# nav10_mxp_3_3_final_expio.net
KiCad netlist of a schematic drawn in EAGLE
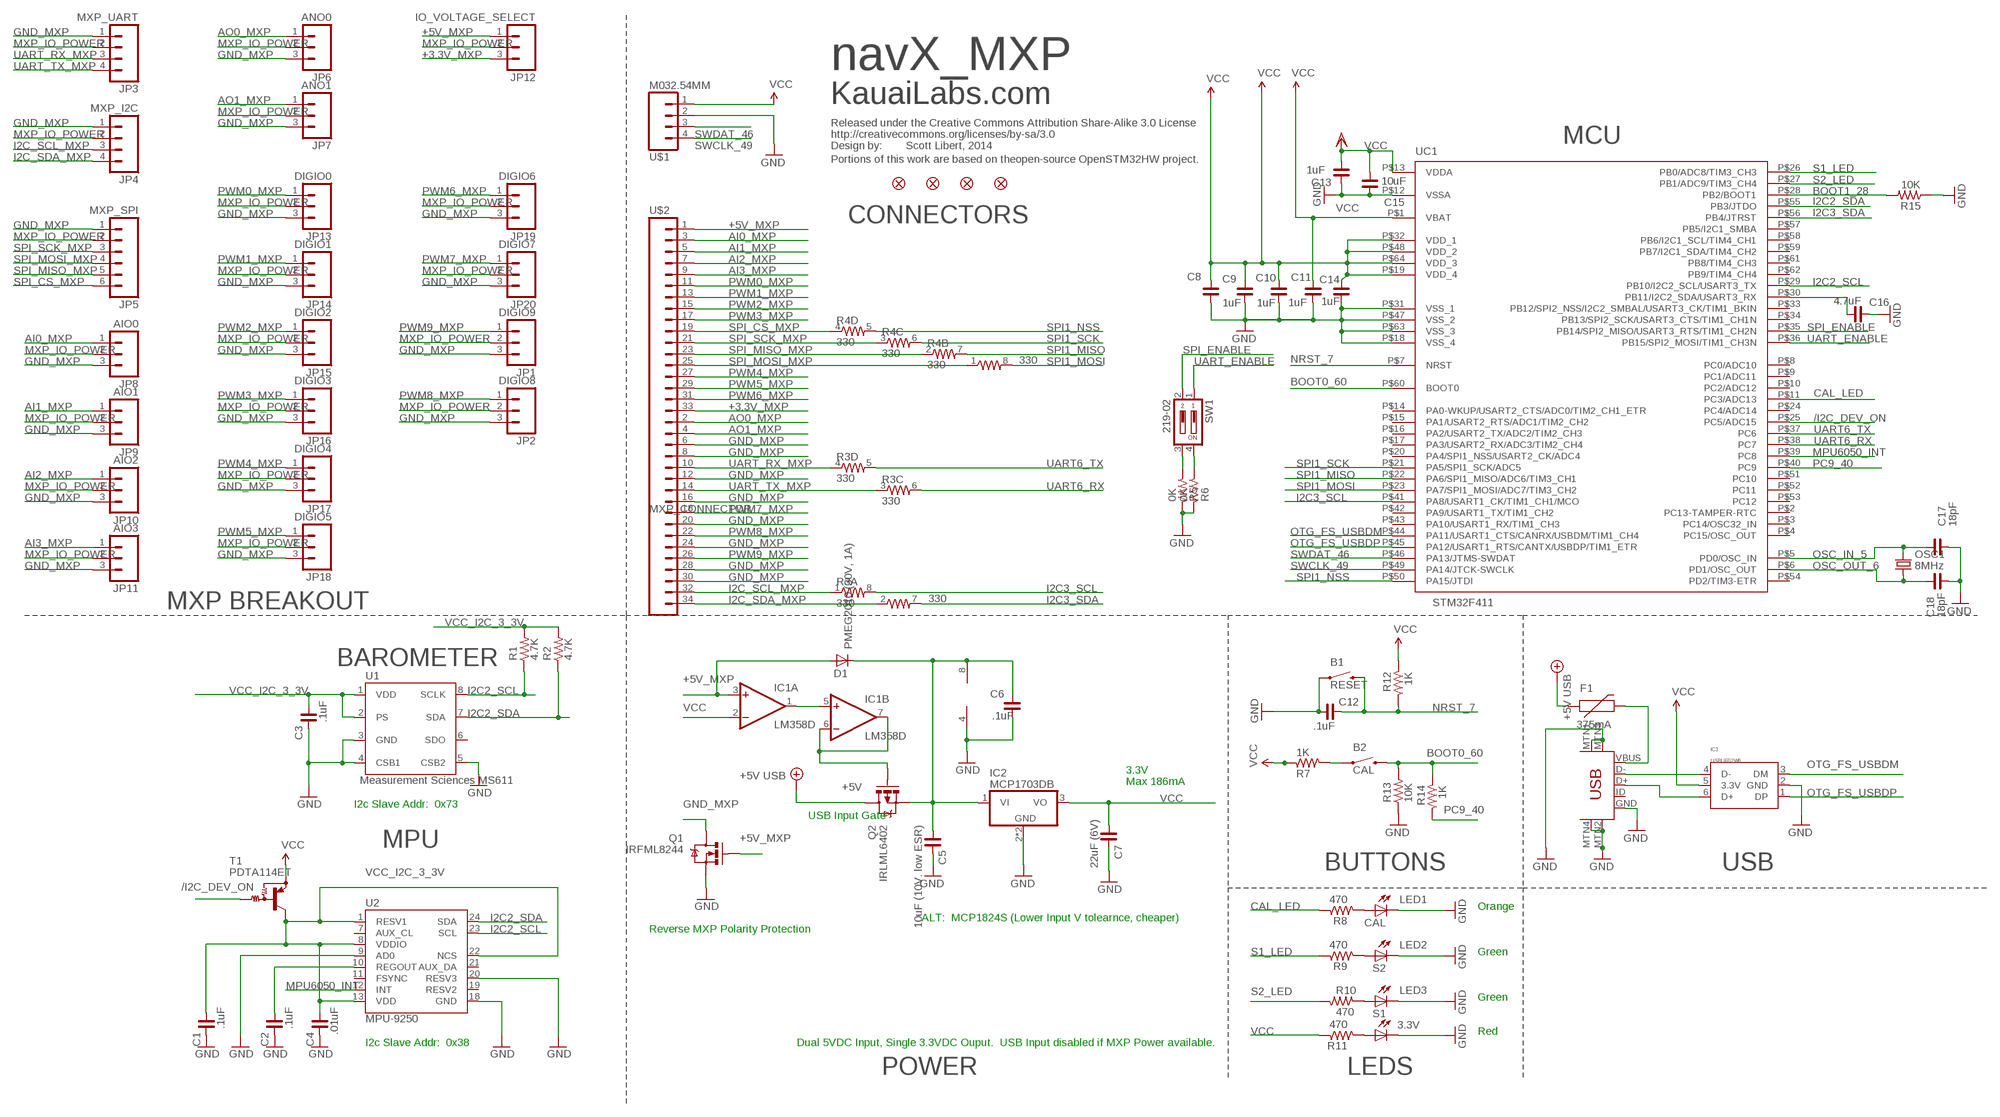
[diagram p0: schematic, sheet 1]

(export (version "E")
  (design (tool "Eeschema 10.0.6"))
  (components
    (comp (ref "B1")
      (value "RESET")
      (footprint "eagle-import:TACTILE-SWITCH-1101NE")
      (libsource (lib "eagle-import") (part "SWITCH-MOMENTARY-2-SMD-1101NE"))
    )
    (comp (ref "B2")
      (value "CAL")
      (footprint "eagle-import:TACTILE-SWITCH-1101NE")
      (libsource (lib "eagle-import") (part "SWITCH-MOMENTARY-2-SMD-1101NE"))
    )
    (comp (ref "C1")
      (value ".1uF")
      (footprint "eagle-import:C0603")
      (libsource (lib "eagle-import") (part "C_0603"))
    )
    (comp (ref "C2")
      (value ".1uF")
      (footprint "eagle-import:C0603")
      (libsource (lib "eagle-import") (part "C_0603"))
    )
    (comp (ref "C3")
      (value ".1uF")
      (footprint "eagle-import:C0603")
      (fields (field (name "DIGIKEY_PART_NUMBER") "399-1096-1-ND"))
      (libsource (lib "eagle-import") (part "C_0603"))
    )
    (comp (ref "C4")
      (value ".01uF")
      (footprint "eagle-import:C0603")
      (libsource (lib "eagle-import") (part "C_0603"))
    )
    (comp (ref "C5")
      (value "10uF (10V. low ESR)")
      (footprint "eagle-import:C0805")
      (fields (field (name "DIGIKEY_PART_NUMBER") "399-1158-1-ND"))
      (libsource (lib "eagle-import") (part "C_0805"))
    )
    (comp (ref "C6")
      (value ".1uF")
      (footprint "eagle-import:C0603")
      (libsource (lib "eagle-import") (part "C_0603"))
    )
    (comp (ref "C7")
      (value "22uF (6V)")
      (footprint "eagle-import:C0805")
      (fields (field (name "DIGIKEY_PART_NUMBER") "399-1158-1-ND"))
      (libsource (lib "eagle-import") (part "C_0805"))
    )
    (comp (ref "C8")
      (value "1uF")
      (footprint "eagle-import:C0603")
      (fields (field (name "DIGIKEY_PART_NUMBER") "399-3118-1-ND"))
      (libsource (lib "eagle-import") (part "C_0603"))
    )
    (comp (ref "C9")
      (value "1uF")
      (footprint "eagle-import:C0603")
      (libsource (lib "eagle-import") (part "C_0603"))
    )
    (comp (ref "C10")
      (value "1uF")
      (footprint "eagle-import:C0603")
      (libsource (lib "eagle-import") (part "C_0603"))
    )
    (comp (ref "C11")
      (value "1uF")
      (footprint "eagle-import:C0603")
      (libsource (lib "eagle-import") (part "C_0603"))
    )
    (comp (ref "C12")
      (value ".1uF")
      (footprint "eagle-import:C0603")
      (libsource (lib "eagle-import") (part "C_0603"))
    )
    (comp (ref "C13")
      (value "1uF")
      (footprint "eagle-import:C0603")
      (libsource (lib "eagle-import") (part "C_0603"))
    )
    (comp (ref "C14")
      (value "1uF")
      (footprint "eagle-import:C0603")
      (libsource (lib "eagle-import") (part "C_0603"))
    )
    (comp (ref "C15")
      (value "10uF")
      (footprint "eagle-import:C0805")
      (libsource (lib "eagle-import") (part "C_0805"))
    )
    (comp (ref "C16")
      (value "4.7uF")
      (footprint "eagle-import:C0603")
      (libsource (lib "eagle-import") (part "C_0603"))
    )
    (comp (ref "C17")
      (value "18pF")
      (footprint "eagle-import:C0603")
      (libsource (lib "eagle-import") (part "C_0603"))
    )
    (comp (ref "C18")
      (value "18pF")
      (footprint "eagle-import:C0603")
      (libsource (lib "eagle-import") (part "C_0603"))
    )
    (comp (ref "D1")
      (value "PMEG2010 (30V, 1A)")
      (footprint "eagle-import:SOD-323")
      (libsource (lib "eagle-import") (part "DIODESOD-323"))
    )
    (comp (ref "F1")
      (value "375mA")
      (footprint "eagle-import:0603")
      (libsource (lib "eagle-import") (part "PTC0603"))
    )
    (comp (ref "IC1")
      (value "LM358D")
      (footprint "eagle-import:SO08")
      (libsource (lib "eagle-import") (part "LM358D"))
    )
    (comp (ref "IC2")
      (value "MCP1703DB")
      (footprint "eagle-import:MCP1703DB")
      (fields (field (name "DIGIKEY_PART_NUMBER") "MCP1703T-3302E/DBCT-ND"))
      (libsource (lib "eagle-import") (part "MCP1703DB"))
    )
    (comp (ref "IC3")
      (value "USBUF02W6")
      (footprint "eagle-import:SC70-6")
      (fields (field (name "DIGIKEY_PART_NUMBER") "497-3743-1-ND"))
      (libsource (lib "eagle-import") (part "USBUF02W6"))
    )
    (comp (ref "JP1")
      (value "DIGIO9")
      (footprint "eagle-import:1X03")
      (libsource (lib "eagle-import") (part "M03PTH"))
    )
    (comp (ref "JP2")
      (value "DIGIO8")
      (footprint "eagle-import:1X03")
      (libsource (lib "eagle-import") (part "M03PTH"))
    )
    (comp (ref "JP3")
      (value "MXP_UART")
      (footprint "eagle-import:1X04")
      (libsource (lib "eagle-import") (part "M04PTH"))
    )
    (comp (ref "JP4")
      (value "MXP_I2C")
      (footprint "eagle-import:1X04")
      (libsource (lib "eagle-import") (part "M04PTH"))
    )
    (comp (ref "JP5")
      (value "MXP_SPI")
      (footprint "eagle-import:1X06")
      (libsource (lib "eagle-import") (part "M06SIP"))
    )
    (comp (ref "JP6")
      (value "ANO0")
      (footprint "eagle-import:1X03")
      (libsource (lib "eagle-import") (part "M03PTH"))
    )
    (comp (ref "JP7")
      (value "ANO1")
      (footprint "eagle-import:1X03")
      (libsource (lib "eagle-import") (part "M03PTH"))
    )
    (comp (ref "JP8")
      (value "AIO0")
      (footprint "eagle-import:1X03")
      (libsource (lib "eagle-import") (part "M03PTH"))
    )
    (comp (ref "JP9")
      (value "AIO1")
      (footprint "eagle-import:1X03")
      (libsource (lib "eagle-import") (part "M03PTH"))
    )
    (comp (ref "JP10")
      (value "AIO2")
      (footprint "eagle-import:1X03")
      (libsource (lib "eagle-import") (part "M03PTH"))
    )
    (comp (ref "JP11")
      (value "AIO3")
      (footprint "eagle-import:1X03")
      (libsource (lib "eagle-import") (part "M03PTH"))
    )
    (comp (ref "JP12")
      (value "IO_VOLTAGE_SELECT")
      (footprint "eagle-import:1X03")
      (libsource (lib "eagle-import") (part "M03PTH"))
    )
    (comp (ref "JP13")
      (value "DIGIO0")
      (footprint "eagle-import:1X03")
      (libsource (lib "eagle-import") (part "M03PTH"))
    )
    (comp (ref "JP14")
      (value "DIGIO1")
      (footprint "eagle-import:1X03")
      (libsource (lib "eagle-import") (part "M03PTH"))
    )
    (comp (ref "JP15")
      (value "DIGIO2")
      (footprint "eagle-import:1X03")
      (libsource (lib "eagle-import") (part "M03PTH"))
    )
    (comp (ref "JP16")
      (value "DIGIO3")
      (footprint "eagle-import:1X03")
      (libsource (lib "eagle-import") (part "M03PTH"))
    )
    (comp (ref "JP17")
      (value "DIGIO4")
      (footprint "eagle-import:1X03")
      (libsource (lib "eagle-import") (part "M03PTH"))
    )
    (comp (ref "JP18")
      (value "DIGIO5")
      (footprint "eagle-import:1X03")
      (libsource (lib "eagle-import") (part "M03PTH"))
    )
    (comp (ref "JP19")
      (value "DIGIO6")
      (footprint "eagle-import:1X03")
      (libsource (lib "eagle-import") (part "M03PTH"))
    )
    (comp (ref "JP20")
      (value "DIGIO7")
      (footprint "eagle-import:1X03")
      (libsource (lib "eagle-import") (part "M03PTH"))
    )
    (comp (ref "JP21")
      (value "FIDUCIAL1X2")
      (footprint "eagle-import:FIDUCIAL-1X2")
      (libsource (lib "eagle-import") (part "FIDUCIAL1X2"))
    )
    (comp (ref "JP22")
      (value "FIDUCIAL1X2")
      (footprint "eagle-import:FIDUCIAL-1X2")
      (libsource (lib "eagle-import") (part "FIDUCIAL1X2"))
    )
    (comp (ref "JP23")
      (value "FIDUCIAL1X2")
      (footprint "eagle-import:FIDUCIAL-1X2")
      (libsource (lib "eagle-import") (part "FIDUCIAL1X2"))
    )
    (comp (ref "JP24")
      (value "FIDUCIAL1X2")
      (footprint "eagle-import:FIDUCIAL-1X2")
      (libsource (lib "eagle-import") (part "FIDUCIAL1X2"))
    )
    (comp (ref "LED1")
      (value "CAL")
      (footprint "eagle-import:CHIP-LED0603")
      (libsource (lib "eagle-import") (part "LEDCHIP-LED0603"))
    )
    (comp (ref "LED2")
      (value "S2")
      (footprint "eagle-import:CHIP-LED0603")
      (libsource (lib "eagle-import") (part "LEDCHIP-LED0603"))
    )
    (comp (ref "LED3")
      (value "S1")
      (footprint "eagle-import:CHIP-LED0603")
      (libsource (lib "eagle-import") (part "LEDCHIP-LED0603"))
    )
    (comp (ref "LED4")
      (value "3.3V")
      (footprint "eagle-import:CHIP-LED0603")
      (libsource (lib "eagle-import") (part "LEDCHIP-LED0603"))
    )
    (comp (ref "LICENSE_TEXT")
      (value "CREATIVE_COMMONS")
      (footprint "eagle-import:CREATIVE_COMMONS")
      (libsource (lib "eagle-import") (part "CREATIVE_COMMONS"))
    )
    (comp (ref "OSC1")
      (value "8MHz")
      (footprint "eagle-import:CRYSTAL-SMD-5X3")
      (libsource (lib "eagle-import") (part "CRYSTAL5X3"))
    )
    (comp (ref "Q1")
      (value "IRFML8244")
      (footprint "eagle-import:SOT23")
      (fields (field (name "DIGIKEY_PART_NUMBER") "DMN3404LDICT-ND"))
      (libsource (lib "eagle-import") (part "MOSFET-NCHANNELBSS123LT1G"))
    )
    (comp (ref "Q2")
      (value "IRLML6402")
      (footprint "eagle-import:SOT23-3")
      (libsource (lib "eagle-import") (part "MOSFET-PCHANNELSMD"))
    )
    (comp (ref "R1")
      (value "4.7K")
      (footprint "eagle-import:R0603")
      (libsource (lib "eagle-import") (part "R_0603"))
    )
    (comp (ref "R2")
      (value "4.7K")
      (footprint "eagle-import:R0603")
      (libsource (lib "eagle-import") (part "R_0603"))
    )
    (comp (ref "R3")
      (value "330")
      (footprint "eagle-import:0603_ARV")
      (fields (field (name "DIGIKEY_PART_NUMBER") "YC164J-1.0KCT-ND"))
      (libsource (lib "eagle-import") (part "RESISTOR-ARRAY0603-ARV"))
    )
    (comp (ref "R4")
      (value "330")
      (footprint "eagle-import:0603_ARV")
      (fields (field (name "DIGIKEY_PART_NUMBER") "YC164J-1.0KCT-ND"))
      (libsource (lib "eagle-import") (part "RESISTOR-ARRAY0603-ARV"))
    )
    (comp (ref "R5")
      (value "0K")
      (footprint "eagle-import:R0603")
      (libsource (lib "eagle-import") (part "R_0603"))
    )
    (comp (ref "R6")
      (value "0K")
      (footprint "eagle-import:R0603")
      (libsource (lib "eagle-import") (part "R_0603"))
    )
    (comp (ref "R7")
      (value "1K")
      (footprint "eagle-import:R0603")
      (libsource (lib "eagle-import") (part "R_0603"))
    )
    (comp (ref "R8")
      (value "470")
      (footprint "eagle-import:R0603")
      (libsource (lib "eagle-import") (part "R_0603"))
    )
    (comp (ref "R9")
      (value "470")
      (footprint "eagle-import:R0603")
      (libsource (lib "eagle-import") (part "R_0603"))
    )
    (comp (ref "R10")
      (value "470")
      (footprint "eagle-import:R0603")
      (libsource (lib "eagle-import") (part "R_0603"))
    )
    (comp (ref "R11")
      (value "470")
      (footprint "eagle-import:R0603")
      (libsource (lib "eagle-import") (part "R_0603"))
    )
    (comp (ref "R12")
      (value "1K")
      (footprint "eagle-import:R0603")
      (libsource (lib "eagle-import") (part "R_0603"))
    )
    (comp (ref "R13")
      (value "10K")
      (footprint "eagle-import:R0603")
      (libsource (lib "eagle-import") (part "R_0603"))
    )
    (comp (ref "R14")
      (value "1K")
      (footprint "eagle-import:R0603")
      (libsource (lib "eagle-import") (part "R_0603"))
    )
    (comp (ref "R15")
      (value "10K")
      (footprint "eagle-import:R0603")
      (libsource (lib "eagle-import") (part "R_0603"))
    )
    (comp (ref "SW1")
      (value "219-02")
      (footprint "eagle-import:CTS-219-02")
      (libsource (lib "eagle-import") (part "219-02"))
    )
    (comp (ref "T1")
      (value "PDTA114ET")
      (footprint "eagle-import:SOT23-3")
      (libsource (lib "eagle-import") (part "PNP-DRIVERSOT23-3"))
    )
    (comp (ref "U$1")
      (value "M032.54MM")
      (footprint "eagle-import:1X04_NO_SILK")
      (libsource (lib "eagle-import") (part "M041X04_NO_SILK"))
    )
    (comp (ref "U$2")
      (value "MXP_CONNECTOR")
      (footprint "eagle-import:2X17")
      (libsource (lib "eagle-import") (part "MXP_CONNECTOR"))
    )
    (comp (ref "U1")
      (value "Measurement Sciences MS611")
      (footprint "eagle-import:MS5611")
      (fields (field (name "DIGIKEY_PART_NUMBER") "MPL115A2-ND"))
      (libsource (lib "eagle-import") (part "MS5611"))
    )
    (comp (ref "U2")
      (value "MPU-9250")
      (footprint "eagle-import:QFN24_3MM_INVENSENSE")
      (fields
        (field (name "DIGIKEY_PART_NUMBER") "1428-1019-1-ND")
        (field (name "MANUFACTURER") "INVENSENSE")
      )
      (libsource (lib "eagle-import") (part "MPU-9250"))
    )
    (comp (ref "UC1")
      (value "STM32F411")
      (footprint "eagle-import:TQFP-10X10-64")
      (fields (field (name "DIGIKEY_PART_NUMBER") "497-11154-ND"))
      (libsource (lib "eagle-import") (part "STM32F103"))
    )
    (comp (ref "USB")
      (value "Mini-USB")
      (footprint "eagle-import:USB-MINIB")
      (fields (field (name "DIGIKEY_PART_NUMBER") "151-1206-1-ND"))
      (libsource (lib "eagle-import") (part "USB-MINIB-5PIN"))
    )
  )
  (nets
    (net (code "1") (name "+5V USB") (class "Default")
      (node (ref "F1") (pin "1") (pinfunction "1_1") (pintype "bidirectional"))
      (node (ref "Q2") (pin "3") (pinfunction "D_3") (pintype "passive"))
    )
    (net (code "2") (name "/+3.3V_MXP") (class "Default")
      (node (ref "JP12") (pin "3") (pinfunction "3_3") (pintype "passive"))
      (node (ref "U$2") (pin "33") (pinfunction "+3.3V_33") (pintype "passive"))
    )
    (net (code "3") (name "/+5V_MXP") (class "Default")
      (node (ref "D1") (pin "A") (pinfunction "A_A") (pintype "passive"))
      (node (ref "IC1") (pin "3") (pinfunction "+IN_3") (pintype "input"))
      (node (ref "JP12") (pin "1") (pinfunction "1_1") (pintype "passive"))
      (node (ref "Q1") (pin "1") (pinfunction "G_1") (pintype "passive"))
      (node (ref "U$2") (pin "1") (pinfunction "+5V_1") (pintype "passive"))
    )
    (net (code "4") (name "/AI0_MXP") (class "Default")
      (node (ref "JP8") (pin "1") (pinfunction "1_1") (pintype "passive"))
      (node (ref "U$2") (pin "3") (pinfunction "AI0_3") (pintype "passive"))
    )
    (net (code "5") (name "/AI1_MXP") (class "Default")
      (node (ref "JP9") (pin "1") (pinfunction "1_1") (pintype "passive"))
      (node (ref "U$2") (pin "5") (pinfunction "AI1_5") (pintype "passive"))
    )
    (net (code "6") (name "/AI2_MXP") (class "Default")
      (node (ref "JP10") (pin "1") (pinfunction "1_1") (pintype "passive"))
      (node (ref "U$2") (pin "7") (pinfunction "AI2_7") (pintype "passive"))
    )
    (net (code "7") (name "/AI3_MXP") (class "Default")
      (node (ref "JP11") (pin "1") (pinfunction "1_1") (pintype "passive"))
      (node (ref "U$2") (pin "9") (pinfunction "AI3_9") (pintype "passive"))
    )
    (net (code "8") (name "/AO0_MXP") (class "Default")
      (node (ref "JP6") (pin "1") (pinfunction "1_1") (pintype "passive"))
      (node (ref "U$2") (pin "2") (pinfunction "AO0_2") (pintype "passive"))
    )
    (net (code "9") (name "/AO1_MXP") (class "Default")
      (node (ref "JP7") (pin "1") (pinfunction "1_1") (pintype "passive"))
      (node (ref "U$2") (pin "4") (pinfunction "AO1_4") (pintype "passive"))
    )
    (net (code "10") (name "/BOOT0_60") (class "Default")
      (node (ref "B2") (pin "P$2") (pinfunction "2_P$2") (pintype "passive"))
      (node (ref "R13") (pin "2") (pinfunction "2_2") (pintype "passive"))
      (node (ref "R14") (pin "1") (pinfunction "1_1") (pintype "passive"))
      (node (ref "UC1") (pin "P$60") (pinfunction "BOOT0_P$60") (pintype "bidirectional"))
    )
    (net (code "11") (name "/BOOT1_28") (class "Default")
      (node (ref "R15") (pin "2") (pinfunction "2_2") (pintype "passive"))
      (node (ref "UC1") (pin "P$28") (pinfunction "PB2/BOOT1_P$28") (pintype "bidirectional"))
    )
    (net (code "12") (name "/CAL_LED") (class "Default")
      (node (ref "R8") (pin "1") (pinfunction "1_1") (pintype "passive"))
      (node (ref "UC1") (pin "P$11") (pinfunction "PC3/ADC13_P$11") (pintype "bidirectional"))
    )
    (net (code "13") (name "/GND_MXP") (class "Default")
      (node (ref "JP1") (pin "3") (pinfunction "3_3") (pintype "passive"))
      (node (ref "JP10") (pin "3") (pinfunction "3_3") (pintype "passive"))
      (node (ref "JP11") (pin "3") (pinfunction "3_3") (pintype "passive"))
      (node (ref "JP13") (pin "3") (pinfunction "3_3") (pintype "passive"))
      (node (ref "JP14") (pin "3") (pinfunction "3_3") (pintype "passive"))
      (node (ref "JP15") (pin "3") (pinfunction "3_3") (pintype "passive"))
      (node (ref "JP16") (pin "3") (pinfunction "3_3") (pintype "passive"))
      (node (ref "JP17") (pin "3") (pinfunction "3_3") (pintype "passive"))
      (node (ref "JP18") (pin "3") (pinfunction "3_3") (pintype "passive"))
      (node (ref "JP19") (pin "3") (pinfunction "3_3") (pintype "passive"))
      (node (ref "JP2") (pin "3") (pinfunction "3_3") (pintype "passive"))
      (node (ref "JP20") (pin "3") (pinfunction "3_3") (pintype "passive"))
      (node (ref "JP3") (pin "1") (pinfunction "1_1") (pintype "passive"))
      (node (ref "JP4") (pin "1") (pinfunction "1_1") (pintype "passive"))
      (node (ref "JP5") (pin "1") (pinfunction "1_1") (pintype "passive"))
      (node (ref "JP6") (pin "3") (pinfunction "3_3") (pintype "passive"))
      (node (ref "JP7") (pin "3") (pinfunction "3_3") (pintype "passive"))
      (node (ref "JP8") (pin "3") (pinfunction "3_3") (pintype "passive"))
      (node (ref "JP9") (pin "3") (pinfunction "3_3") (pintype "passive"))
      (node (ref "Q1") (pin "3") (pinfunction "D_3") (pintype "passive"))
      (node (ref "U$2") (pin "12") (pinfunction "GND3_12") (pintype "passive"))
      (node (ref "U$2") (pin "16") (pinfunction "GND4_16") (pintype "passive"))
      (node (ref "U$2") (pin "20") (pinfunction "GND5_20") (pintype "passive"))
      (node (ref "U$2") (pin "24") (pinfunction "GND6_24") (pintype "passive"))
      (node (ref "U$2") (pin "28") (pinfunction "GND7_28") (pintype "passive"))
      (node (ref "U$2") (pin "30") (pinfunction "GND8_30") (pintype "passive"))
      (node (ref "U$2") (pin "6") (pinfunction "GND1_6") (pintype "passive"))
      (node (ref "U$2") (pin "8") (pinfunction "GND2_8") (pintype "passive"))
    )
    (net (code "14") (name "/I2C2_SCL") (class "Default")
      (node (ref "R1") (pin "1") (pinfunction "1_1") (pintype "passive"))
      (node (ref "U1") (pin "8") (pinfunction "SCLK_8") (pintype "bidirectional"))
      (node (ref "U2") (pin "23") (pinfunction "SCL_23") (pintype "bidirectional"))
      (node (ref "UC1") (pin "P$29") (pinfunction "PB10/I2C2_SCL/USART3_TX_P$29") (pintype "bidirectional"))
    )
    (net (code "15") (name "/I2C2_SDA") (class "Default")
      (node (ref "R2") (pin "1") (pinfunction "1_1") (pintype "passive"))
      (node (ref "U1") (pin "7") (pinfunction "SDA_7") (pintype "bidirectional"))
      (node (ref "U2") (pin "24") (pinfunction "SDA_24") (pintype "bidirectional"))
      (node (ref "UC1") (pin "P$55") (pinfunction "PB3/JTDO_P$55") (pintype "bidirectional"))
    )
    (net (code "16") (name "/I2C3_SCL") (class "Default")
      (node (ref "R3") (pin "8") (pinfunction "2_8") (pintype "passive"))
      (node (ref "UC1") (pin "P$41") (pinfunction "PA8/USART1_CK/TIM1_CH1/MCO_P$41") (pintype "bidirectional"))
    )
    (net (code "17") (name "/I2C3_SDA") (class "Default")
      (node (ref "R3") (pin "7") (pinfunction "2_7") (pintype "passive"))
      (node (ref "UC1") (pin "P$56") (pinfunction "PB4/JTRST_P$56") (pintype "bidirectional"))
    )
    (net (code "18") (name "/I2C_SCL_MXP") (class "Default")
      (node (ref "JP4") (pin "3") (pinfunction "3_3") (pintype "passive"))
      (node (ref "R3") (pin "1") (pinfunction "1_1") (pintype "passive"))
      (node (ref "U$2") (pin "32") (pinfunction "DIO14/I2C_SCL_32") (pintype "passive"))
    )
    (net (code "19") (name "/I2C_SDA_MXP") (class "Default")
      (node (ref "JP4") (pin "4") (pinfunction "4_4") (pintype "passive"))
      (node (ref "R3") (pin "2") (pinfunction "1_2") (pintype "passive"))
      (node (ref "U$2") (pin "34") (pinfunction "DIO15/I2C_SDA_34") (pintype "passive"))
    )
    (net (code "20") (name "/MPU6050_INT") (class "Default")
      (node (ref "U2") (pin "12") (pinfunction "INT_12") (pintype "bidirectional"))
      (node (ref "UC1") (pin "P$39") (pinfunction "PC8_P$39") (pintype "bidirectional"))
    )
    (net (code "21") (name "/MXP_IO_POWER") (class "Default")
      (node (ref "JP1") (pin "2") (pinfunction "2_2") (pintype "passive"))
      (node (ref "JP10") (pin "2") (pinfunction "2_2") (pintype "passive"))
      (node (ref "JP11") (pin "2") (pinfunction "2_2") (pintype "passive"))
      (node (ref "JP12") (pin "2") (pinfunction "2_2") (pintype "passive"))
      (node (ref "JP13") (pin "2") (pinfunction "2_2") (pintype "passive"))
      (node (ref "JP14") (pin "2") (pinfunction "2_2") (pintype "passive"))
      (node (ref "JP15") (pin "2") (pinfunction "2_2") (pintype "passive"))
      (node (ref "JP16") (pin "2") (pinfunction "2_2") (pintype "passive"))
      (node (ref "JP17") (pin "2") (pinfunction "2_2") (pintype "passive"))
      (node (ref "JP18") (pin "2") (pinfunction "2_2") (pintype "passive"))
      (node (ref "JP19") (pin "2") (pinfunction "2_2") (pintype "passive"))
      (node (ref "JP2") (pin "2") (pinfunction "2_2") (pintype "passive"))
      (node (ref "JP20") (pin "2") (pinfunction "2_2") (pintype "passive"))
      (node (ref "JP3") (pin "2") (pinfunction "2_2") (pintype "passive"))
      (node (ref "JP4") (pin "2") (pinfunction "2_2") (pintype "passive"))
      (node (ref "JP5") (pin "2") (pinfunction "2_2") (pintype "passive"))
      (node (ref "JP6") (pin "2") (pinfunction "2_2") (pintype "passive"))
      (node (ref "JP7") (pin "2") (pinfunction "2_2") (pintype "passive"))
      (node (ref "JP8") (pin "2") (pinfunction "2_2") (pintype "passive"))
      (node (ref "JP9") (pin "2") (pinfunction "2_2") (pintype "passive"))
    )
    (net (code "22") (name "/NRST_7") (class "Default")
      (node (ref "B1") (pin "P$2") (pinfunction "2_P$2") (pintype "passive"))
      (node (ref "C12") (pin "2") (pinfunction "2_2") (pintype "passive"))
      (node (ref "R12") (pin "2") (pinfunction "2_2") (pintype "passive"))
      (node (ref "UC1") (pin "P$7") (pinfunction "NRST_P$7") (pintype "bidirectional"))
    )
    (net (code "23") (name "/OSC_IN_5") (class "Default")
      (node (ref "C17") (pin "2") (pinfunction "2_2") (pintype "passive"))
      (node (ref "OSC1") (pin "3") (pinfunction "2_3") (pintype "passive"))
      (node (ref "UC1") (pin "P$5") (pinfunction "PD0/OSC_IN_P$5") (pintype "bidirectional"))
    )
    (net (code "24") (name "/OSC_OUT_6") (class "Default")
      (node (ref "C18") (pin "2") (pinfunction "2_2") (pintype "passive"))
      (node (ref "OSC1") (pin "1") (pinfunction "1_1") (pintype "passive"))
      (node (ref "UC1") (pin "P$6") (pinfunction "PD1/OSC_OUT_P$6") (pintype "bidirectional"))
    )
    (net (code "25") (name "/OTG_FS_USBDM") (class "Default")
      (node (ref "IC3") (pin "3") (pinfunction "DM_3") (pintype "bidirectional"))
      (node (ref "UC1") (pin "P$44") (pinfunction "PA11/USART1_CTS/CANRX/USBDM/TIM1_CH4_P$44") (pintype "bidirectional"))
    )
    (net (code "26") (name "/OTG_FS_USBDP") (class "Default")
      (node (ref "IC3") (pin "1") (pinfunction "DP_1") (pintype "bidirectional"))
      (node (ref "UC1") (pin "P$45") (pinfunction "PA12/USART1_RTS/CANTX/USBDP/TIM1_ETR_P$45") (pintype "bidirectional"))
    )
    (net (code "27") (name "/PC9_40") (class "Default")
      (node (ref "R14") (pin "2") (pinfunction "2_2") (pintype "passive"))
      (node (ref "UC1") (pin "P$40") (pinfunction "PC9_P$40") (pintype "bidirectional"))
    )
    (net (code "28") (name "/PWM0_MXP") (class "Default")
      (node (ref "JP13") (pin "1") (pinfunction "1_1") (pintype "passive"))
      (node (ref "U$2") (pin "11") (pinfunction "DIO0/PWM0_11") (pintype "passive"))
    )
    (net (code "29") (name "/PWM1_MXP") (class "Default")
      (node (ref "JP14") (pin "1") (pinfunction "1_1") (pintype "passive"))
      (node (ref "U$2") (pin "13") (pinfunction "DIO1/PWM1_13") (pintype "passive"))
    )
    (net (code "30") (name "/PWM2_MXP") (class "Default")
      (node (ref "JP15") (pin "1") (pinfunction "1_1") (pintype "passive"))
      (node (ref "U$2") (pin "15") (pinfunction "DIO2/PWM2_15") (pintype "passive"))
    )
    (net (code "31") (name "/PWM3_MXP") (class "Default")
      (node (ref "JP16") (pin "1") (pinfunction "1_1") (pintype "passive"))
      (node (ref "U$2") (pin "17") (pinfunction "DIO3/PWM3_17") (pintype "passive"))
    )
    (net (code "32") (name "/PWM4_MXP") (class "Default")
      (node (ref "JP17") (pin "1") (pinfunction "1_1") (pintype "passive"))
      (node (ref "U$2") (pin "27") (pinfunction "DIO8/PWM4_27") (pintype "passive"))
    )
    (net (code "33") (name "/PWM5_MXP") (class "Default")
      (node (ref "JP18") (pin "1") (pinfunction "1_1") (pintype "passive"))
      (node (ref "U$2") (pin "29") (pinfunction "DIO9/PWM5_29") (pintype "passive"))
    )
    (net (code "34") (name "/PWM6_MXP") (class "Default")
      (node (ref "JP19") (pin "1") (pinfunction "1_1") (pintype "passive"))
      (node (ref "U$2") (pin "31") (pinfunction "DIO10/PWM6_31") (pintype "passive"))
    )
    (net (code "35") (name "/PWM7_MXP") (class "Default")
      (node (ref "JP20") (pin "1") (pinfunction "1_1") (pintype "passive"))
      (node (ref "U$2") (pin "18") (pinfunction "DIO11/PWM11_18") (pintype "passive"))
    )
    (net (code "36") (name "/PWM8_MXP") (class "Default")
      (node (ref "JP2") (pin "1") (pinfunction "1_1") (pintype "passive"))
      (node (ref "U$2") (pin "22") (pinfunction "DIO12/PWM12_22") (pintype "passive"))
    )
    (net (code "37") (name "/PWM9_MXP") (class "Default")
      (node (ref "JP1") (pin "1") (pinfunction "1_1") (pintype "passive"))
      (node (ref "U$2") (pin "26") (pinfunction "DIO13/PWM13_26") (pintype "passive"))
    )
    (net (code "38") (name "/S1_LED") (class "Default")
      (node (ref "R9") (pin "1") (pinfunction "1_1") (pintype "passive"))
      (node (ref "UC1") (pin "P$26") (pinfunction "PB0/ADC8/TIM3_CH3_P$26") (pintype "bidirectional"))
    )
    (net (code "39") (name "/S2_LED") (class "Default")
      (node (ref "R10") (pin "2") (pinfunction "2_2") (pintype "passive"))
      (node (ref "UC1") (pin "P$27") (pinfunction "PB1/ADC9/TIM3_CH4_P$27") (pintype "bidirectional"))
    )
    (net (code "40") (name "/SPI1_MISO") (class "Default")
      (node (ref "R4") (pin "7") (pinfunction "2_7") (pintype "passive"))
      (node (ref "UC1") (pin "P$22") (pinfunction "PA6/SPI1_MISO/ADC6/TIM3_CH1_P$22") (pintype "bidirectional"))
    )
    (net (code "41") (name "/SPI1_MOSI") (class "Default")
      (node (ref "R4") (pin "8") (pinfunction "2_8") (pintype "passive"))
      (node (ref "UC1") (pin "P$23") (pinfunction "PA7/SPI1_MOSI/ADC7/TIM3_CH2_P$23") (pintype "bidirectional"))
    )
    (net (code "42") (name "/SPI1_NSS") (class "Default")
      (node (ref "R4") (pin "5") (pinfunction "2_5") (pintype "passive"))
      (node (ref "UC1") (pin "P$50") (pinfunction "PA15/JTDI_P$50") (pintype "bidirectional"))
    )
    (net (code "43") (name "/SPI1_SCK") (class "Default")
      (node (ref "R4") (pin "6") (pinfunction "2_6") (pintype "passive"))
      (node (ref "UC1") (pin "P$21") (pinfunction "PA5/SPI1_SCK/ADC5_P$21") (pintype "bidirectional"))
    )
    (net (code "44") (name "/SPI_CS_MXP") (class "Default")
      (node (ref "JP5") (pin "6") (pinfunction "6_6") (pintype "passive"))
      (node (ref "R4") (pin "4") (pinfunction "1_4") (pintype "passive"))
      (node (ref "U$2") (pin "19") (pinfunction "DIO4/SPICS_19") (pintype "passive"))
    )
    (net (code "45") (name "/SPI_ENABLE") (class "Default")
      (node (ref "SW1") (pin "2") (pinfunction "2_2") (pintype "passive"))
      (node (ref "UC1") (pin "P$35") (pinfunction "PB14/SPI2_MISO/USART3_RTS/TIM1_CH2N_P$35") (pintype "bidirectional"))
    )
    (net (code "46") (name "/SPI_MISO_MXP") (class "Default")
      (node (ref "JP5") (pin "5") (pinfunction "5_5") (pintype "passive"))
      (node (ref "R4") (pin "2") (pinfunction "1_2") (pintype "passive"))
      (node (ref "U$2") (pin "23") (pinfunction "DIO6/SPIMISO_23") (pintype "passive"))
    )
    (net (code "47") (name "/SPI_MOSI_MXP") (class "Default")
      (node (ref "JP5") (pin "4") (pinfunction "4_4") (pintype "passive"))
      (node (ref "R4") (pin "1") (pinfunction "1_1") (pintype "passive"))
      (node (ref "U$2") (pin "25") (pinfunction "DIO7/SPIMOSI_25") (pintype "passive"))
    )
    (net (code "48") (name "/SPI_SCK_MXP") (class "Default")
      (node (ref "JP5") (pin "3") (pinfunction "3_3") (pintype "passive"))
      (node (ref "R4") (pin "3") (pinfunction "1_3") (pintype "passive"))
      (node (ref "U$2") (pin "21") (pinfunction "DIO5/SPICLK_21") (pintype "passive"))
    )
    (net (code "49") (name "/SWCLK_49") (class "Default")
      (node (ref "U$1") (pin "4") (pinfunction "4_4") (pintype "passive"))
      (node (ref "UC1") (pin "P$49") (pinfunction "PA14/JTCK-SWCLK_P$49") (pintype "bidirectional"))
    )
    (net (code "50") (name "/SWDAT_46") (class "Default")
      (node (ref "U$1") (pin "3") (pinfunction "3_3") (pintype "passive"))
      (node (ref "UC1") (pin "P$46") (pinfunction "PA13/JTMS-SWDAT_P$46") (pintype "bidirectional"))
    )
    (net (code "51") (name "/UART6_RX") (class "Default")
      (node (ref "R3") (pin "6") (pinfunction "2_6") (pintype "passive"))
      (node (ref "UC1") (pin "P$38") (pinfunction "PC7_P$38") (pintype "bidirectional"))
    )
    (net (code "52") (name "/UART6_TX") (class "Default")
      (node (ref "R3") (pin "5") (pinfunction "2_5") (pintype "passive"))
      (node (ref "UC1") (pin "P$37") (pinfunction "PC6_P$37") (pintype "bidirectional"))
    )
    (net (code "53") (name "/UART_ENABLE") (class "Default")
      (node (ref "SW1") (pin "1") (pinfunction "1_1") (pintype "passive"))
      (node (ref "UC1") (pin "P$36") (pinfunction "PB15/SPI2_MOSI/TIM1_CH3N_P$36") (pintype "bidirectional"))
    )
    (net (code "54") (name "/UART_RX_MXP") (class "Default")
      (node (ref "JP3") (pin "3") (pinfunction "3_3") (pintype "passive"))
      (node (ref "R3") (pin "4") (pinfunction "1_4") (pintype "passive"))
      (node (ref "U$2") (pin "10") (pinfunction "UART.RX_10") (pintype "passive"))
    )
    (net (code "55") (name "/UART_TX_MXP") (class "Default")
      (node (ref "JP3") (pin "4") (pinfunction "4_4") (pintype "passive"))
      (node (ref "R3") (pin "3") (pinfunction "1_3") (pintype "passive"))
      (node (ref "U$2") (pin "14") (pinfunction "UART.TX_14") (pintype "passive"))
    )
    (net (code "56") (name "/VCC_I2C_3_3V") (class "Default")
      (node (ref "C1") (pin "1") (pinfunction "1_1") (pintype "passive"))
      (node (ref "C3") (pin "1") (pinfunction "1_1") (pintype "passive"))
      (node (ref "C4") (pin "1") (pinfunction "1_1") (pintype "passive"))
      (node (ref "R1") (pin "2") (pinfunction "2_2") (pintype "passive"))
      (node (ref "R2") (pin "2") (pinfunction "2_2") (pintype "passive"))
      (node (ref "T1") (pin "3") (pinfunction "C_3") (pintype "passive"))
      (node (ref "U1") (pin "1") (pinfunction "VDD_1") (pintype "bidirectional"))
      (node (ref "U1") (pin "2") (pinfunction "PS_2") (pintype "bidirectional"))
      (node (ref "U2") (pin "1") (pinfunction "RESV1_1") (pintype "bidirectional"))
      (node (ref "U2") (pin "13") (pinfunction "VDD_13") (pintype "bidirectional"))
      (node (ref "U2") (pin "22") (pinfunction "NCS_22") (pintype "bidirectional"))
      (node (ref "U2") (pin "8") (pinfunction "VDDIO_8") (pintype "bidirectional"))
    )
    (net (code "57") (name "/{slash}I2C_DEV_ON") (class "Default")
      (node (ref "T1") (pin "1") (pinfunction "B_1") (pintype "passive"))
      (node (ref "UC1") (pin "P$25") (pinfunction "PC5/ADC15_P$25") (pintype "bidirectional"))
    )
    (net (code "58") (name "GND") (class "Default")
      (node (ref "B1") (pin "P$1") (pinfunction "1_P$1") (pintype "passive"))
      (node (ref "C1") (pin "2") (pinfunction "2_2") (pintype "passive"))
      (node (ref "C10") (pin "1") (pinfunction "1_1") (pintype "passive"))
      (node (ref "C11") (pin "1") (pinfunction "1_1") (pintype "passive"))
      (node (ref "C12") (pin "1") (pinfunction "1_1") (pintype "passive"))
      (node (ref "C13") (pin "1") (pinfunction "1_1") (pintype "passive"))
      (node (ref "C14") (pin "1") (pinfunction "1_1") (pintype "passive"))
      (node (ref "C15") (pin "2") (pinfunction "2_2") (pintype "passive"))
      (node (ref "C16") (pin "1") (pinfunction "1_1") (pintype "passive"))
      (node (ref "C17") (pin "1") (pinfunction "1_1") (pintype "passive"))
      (node (ref "C18") (pin "1") (pinfunction "1_1") (pintype "passive"))
      (node (ref "C2") (pin "2") (pinfunction "2_2") (pintype "passive"))
      (node (ref "C3") (pin "2") (pinfunction "2_2") (pintype "passive"))
      (node (ref "C4") (pin "2") (pinfunction "2_2") (pintype "passive"))
      (node (ref "C5") (pin "2") (pinfunction "2_2") (pintype "passive"))
      (node (ref "C6") (pin "1") (pinfunction "1_1") (pintype "passive"))
      (node (ref "C7") (pin "2") (pinfunction "2_2") (pintype "passive"))
      (node (ref "C8") (pin "1") (pinfunction "1_1") (pintype "passive"))
      (node (ref "C9") (pin "1") (pinfunction "1_1") (pintype "passive"))
      (node (ref "IC1") (pin "4") (pinfunction "V-_4") (pintype "power_in"))
      (node (ref "IC2") (pin "2") (pinfunction "GND_2") (pintype "passive"))
      (node (ref "IC2") (pin "4") (pinfunction "GND_4") (pintype "passive"))
      (node (ref "IC3") (pin "2") (pinfunction "GND_2") (pintype "bidirectional"))
      (node (ref "LED1") (pin "C") (pinfunction "C_C") (pintype "passive"))
      (node (ref "LED2") (pin "C") (pinfunction "C_C") (pintype "passive"))
      (node (ref "LED3") (pin "C") (pinfunction "C_C") (pintype "passive"))
      (node (ref "LED4") (pin "C") (pinfunction "C_C") (pintype "passive"))
      (node (ref "Q1") (pin "2") (pinfunction "S_2") (pintype "passive"))
      (node (ref "R13") (pin "1") (pinfunction "1_1") (pintype "passive"))
      (node (ref "R15") (pin "1") (pinfunction "1_1") (pintype "passive"))
      (node (ref "R5") (pin "1") (pinfunction "1_1") (pintype "passive"))
      (node (ref "R6") (pin "1") (pinfunction "1_1") (pintype "passive"))
      (node (ref "U$1") (pin "2") (pinfunction "2_2") (pintype "passive"))
      (node (ref "U1") (pin "3") (pinfunction "GND_3") (pintype "bidirectional"))
      (node (ref "U1") (pin "4") (pinfunction "CSB1_4") (pintype "bidirectional"))
      (node (ref "U1") (pin "5") (pinfunction "CSB2_5") (pintype "bidirectional"))
      (node (ref "U2") (pin "18") (pinfunction "GND_18") (pintype "bidirectional"))
      (node (ref "U2") (pin "20") (pinfunction "RESV3_20") (pintype "bidirectional"))
      (node (ref "U2") (pin "9") (pinfunction "AD0_9") (pintype "bidirectional"))
      (node (ref "UC1") (pin "P$12") (pinfunction "VSSA_P$12") (pintype "power_in"))
      (node (ref "UC1") (pin "P$18") (pinfunction "VSS_4_P$18") (pintype "power_in"))
      (node (ref "UC1") (pin "P$31") (pinfunction "VSS_1_P$31") (pintype "power_in"))
      (node (ref "UC1") (pin "P$47") (pinfunction "VSS_2_P$47") (pintype "power_in"))
      (node (ref "UC1") (pin "P$63") (pinfunction "VSS_3_P$63") (pintype "power_in"))
      (node (ref "USB") (pin "GND") (pinfunction "GND_GND") (pintype "bidirectional"))
      (node (ref "USB") (pin "MTN1") (pinfunction "MTN2_MTN1") (pintype "bidirectional"))
      (node (ref "USB") (pin "MTN2") (pinfunction "MTN3_MTN2") (pintype "bidirectional"))
      (node (ref "USB") (pin "MTN3") (pinfunction "MTN1_MTN3") (pintype "bidirectional"))
      (node (ref "USB") (pin "MTN4") (pinfunction "MTN4_MTN4") (pintype "bidirectional"))
    )
    (net (code "59") (name "Net-(B2-1)") (class "Default")
      (node (ref "B2") (pin "P$1") (pinfunction "1_P$1") (pintype "passive"))
      (node (ref "R7") (pin "2") (pinfunction "2_2") (pintype "passive"))
    )
    (net (code "60") (name "Net-(F1-Pad2)") (class "Default")
      (node (ref "F1") (pin "2") (pinfunction "2_2") (pintype "bidirectional"))
      (node (ref "USB") (pin "VBUS") (pinfunction "VBUS_VBUS") (pintype "bidirectional"))
    )
    (net (code "61") (name "Net-(IC1A-OUT)") (class "Default")
      (node (ref "IC1") (pin "1") (pinfunction "OUT_1") (pintype "output"))
      (node (ref "IC1") (pin "5") (pinfunction "+IN_5") (pintype "input"))
    )
    (net (code "62") (name "Net-(IC1B--IN)") (class "Default")
      (node (ref "IC1") (pin "6") (pinfunction "-IN_6") (pintype "input"))
      (node (ref "IC1") (pin "7") (pinfunction "OUT_7") (pintype "output"))
      (node (ref "Q2") (pin "1") (pinfunction "G_1") (pintype "passive"))
    )
    (net (code "63") (name "Net-(IC1C-V+)") (class "Default")
      (node (ref "C5") (pin "1") (pinfunction "1_1") (pintype "passive"))
      (node (ref "C6") (pin "2") (pinfunction "2_2") (pintype "passive"))
      (node (ref "D1") (pin "C") (pinfunction "C_C") (pintype "passive"))
      (node (ref "IC1") (pin "8") (pinfunction "V+_8") (pintype "power_in"))
      (node (ref "IC2") (pin "1") (pinfunction "VI_1") (pintype "input"))
      (node (ref "Q2") (pin "2") (pinfunction "S_2") (pintype "passive"))
    )
    (net (code "64") (name "Net-(IC3-D+)") (class "Default")
      (node (ref "IC3") (pin "6") (pinfunction "D+_6") (pintype "bidirectional"))
      (node (ref "USB") (pin "D+") (pinfunction "D+_D+") (pintype "bidirectional"))
    )
    (net (code "65") (name "Net-(IC3-D-)") (class "Default")
      (node (ref "IC3") (pin "4") (pinfunction "D-_4") (pintype "bidirectional"))
      (node (ref "USB") (pin "D-") (pinfunction "D-_D-") (pintype "bidirectional"))
    )
    (net (code "66") (name "Net-(LED1-PadA)") (class "Default")
      (node (ref "LED1") (pin "A") (pinfunction "A_A") (pintype "passive"))
      (node (ref "R8") (pin "2") (pinfunction "2_2") (pintype "passive"))
    )
    (net (code "67") (name "Net-(LED2-PadA)") (class "Default")
      (node (ref "LED2") (pin "A") (pinfunction "A_A") (pintype "passive"))
      (node (ref "R9") (pin "2") (pinfunction "2_2") (pintype "passive"))
    )
    (net (code "68") (name "Net-(LED3-PadA)") (class "Default")
      (node (ref "LED3") (pin "A") (pinfunction "A_A") (pintype "passive"))
      (node (ref "R10") (pin "1") (pinfunction "1_1") (pintype "passive"))
    )
    (net (code "69") (name "Net-(LED4-PadA)") (class "Default")
      (node (ref "LED4") (pin "A") (pinfunction "A_A") (pintype "passive"))
      (node (ref "R11") (pin "2") (pinfunction "2_2") (pintype "passive"))
    )
    (net (code "70") (name "Net-(R5-Pad2)") (class "Default")
      (node (ref "R5") (pin "2") (pinfunction "2_2") (pintype "passive"))
      (node (ref "SW1") (pin "3") (pinfunction "3_3") (pintype "passive"))
    )
    (net (code "71") (name "Net-(R6-Pad2)") (class "Default")
      (node (ref "R6") (pin "2") (pinfunction "2_2") (pintype "passive"))
      (node (ref "SW1") (pin "4") (pinfunction "4_4") (pintype "passive"))
    )
    (net (code "72") (name "Net-(U2-REGOUT)") (class "Default")
      (node (ref "C2") (pin "1") (pinfunction "1_1") (pintype "passive"))
      (node (ref "U2") (pin "10") (pinfunction "REGOUT_10") (pintype "bidirectional"))
    )
    (net (code "73") (name "Net-(UC1-PB11{slash}I2C2_SDA{slash}USART3_RX)") (class "Default")
      (node (ref "C16") (pin "2") (pinfunction "2_2") (pintype "passive"))
      (node (ref "UC1") (pin "P$30") (pinfunction "PB11/I2C2_SDA/USART3_RX_P$30") (pintype "bidirectional"))
    )
    (net (code "74") (name "VCC") (class "Default")
      (node (ref "C10") (pin "2") (pinfunction "2_2") (pintype "passive"))
      (node (ref "C11") (pin "2") (pinfunction "2_2") (pintype "passive"))
      (node (ref "C13") (pin "2") (pinfunction "2_2") (pintype "passive"))
      (node (ref "C14") (pin "2") (pinfunction "2_2") (pintype "passive"))
      (node (ref "C15") (pin "1") (pinfunction "1_1") (pintype "passive"))
      (node (ref "C7") (pin "1") (pinfunction "1_1") (pintype "passive"))
      (node (ref "C8") (pin "2") (pinfunction "2_2") (pintype "passive"))
      (node (ref "C9") (pin "2") (pinfunction "2_2") (pintype "passive"))
      (node (ref "IC1") (pin "2") (pinfunction "-IN_2") (pintype "input"))
      (node (ref "IC2") (pin "3") (pinfunction "VO_3") (pintype "passive"))
      (node (ref "IC3") (pin "5") (pinfunction "3.3V_5") (pintype "bidirectional"))
      (node (ref "R11") (pin "1") (pinfunction "1_1") (pintype "passive"))
      (node (ref "R12") (pin "1") (pinfunction "1_1") (pintype "passive"))
      (node (ref "R7") (pin "1") (pinfunction "1_1") (pintype "passive"))
      (node (ref "T1") (pin "2") (pinfunction "E_2") (pintype "passive"))
      (node (ref "U$1") (pin "1") (pinfunction "1_1") (pintype "passive"))
      (node (ref "UC1") (pin "P$1") (pinfunction "VBAT_P$1") (pintype "power_in"))
      (node (ref "UC1") (pin "P$13") (pinfunction "VDDA_P$13") (pintype "power_in"))
      (node (ref "UC1") (pin "P$19") (pinfunction "VDD_4_P$19") (pintype "power_in"))
      (node (ref "UC1") (pin "P$32") (pinfunction "VDD_1_P$32") (pintype "power_in"))
      (node (ref "UC1") (pin "P$48") (pinfunction "VDD_2_P$48") (pintype "power_in"))
      (node (ref "UC1") (pin "P$64") (pinfunction "VDD_3_P$64") (pintype "power_in"))
    )
    (net (code "75") (name "unconnected-(U1-SDO-Pad6)") (class "Default")
      (node (ref "U1") (pin "6") (pinfunction "SDO_6") (pintype "bidirectional"))
    )
    (net (code "76") (name "unconnected-(U2-AUX_CL-Pad7)") (class "Default")
      (node (ref "U2") (pin "7") (pinfunction "AUX_CL_7") (pintype "bidirectional"))
    )
    (net (code "77") (name "unconnected-(U2-AUX_DA-Pad21)") (class "Default")
      (node (ref "U2") (pin "21") (pinfunction "AUX_DA_21") (pintype "bidirectional"))
    )
    (net (code "78") (name "unconnected-(U2-FSYNC-Pad11)") (class "Default")
      (node (ref "U2") (pin "11") (pinfunction "FSYNC_11") (pintype "bidirectional"))
    )
    (net (code "79") (name "unconnected-(U2-RESV2-Pad19)") (class "Default")
      (node (ref "U2") (pin "19") (pinfunction "RESV2_19") (pintype "bidirectional"))
    )
    (net (code "80") (name "unconnected-(UC1-PA0-WKUP{slash}USART2_CTS{slash}ADC0{slash}TIM2_CH1_ETR-PadP$14)") (class "Default")
      (node (ref "UC1") (pin "P$14") (pinfunction "PA0-WKUP/USART2_CTS/ADC0/TIM2_CH1_ETR_P$14") (pintype "bidirectional"))
    )
    (net (code "81") (name "unconnected-(UC1-PA1{slash}USART2_RTS{slash}ADC1{slash}TIM2_CH2-PadP$15)") (class "Default")
      (node (ref "UC1") (pin "P$15") (pinfunction "PA1/USART2_RTS/ADC1/TIM2_CH2_P$15") (pintype "bidirectional"))
    )
    (net (code "82") (name "unconnected-(UC1-PA2{slash}USART2_TX{slash}ADC2{slash}TIM2_CH3-PadP$16)") (class "Default")
      (node (ref "UC1") (pin "P$16") (pinfunction "PA2/USART2_TX/ADC2/TIM2_CH3_P$16") (pintype "bidirectional"))
    )
    (net (code "83") (name "unconnected-(UC1-PA3{slash}USART2_RX{slash}ADC3{slash}TIM2_CH4-PadP$17)") (class "Default")
      (node (ref "UC1") (pin "P$17") (pinfunction "PA3/USART2_RX/ADC3/TIM2_CH4_P$17") (pintype "bidirectional"))
    )
    (net (code "84") (name "unconnected-(UC1-PA4{slash}SPI1_NSS{slash}USART2_CK{slash}ADC4-PadP$20)") (class "Default")
      (node (ref "UC1") (pin "P$20") (pinfunction "PA4/SPI1_NSS/USART2_CK/ADC4_P$20") (pintype "bidirectional"))
    )
    (net (code "85") (name "unconnected-(UC1-PA9{slash}USART1_TX{slash}TIM1_CH2-PadP$42)") (class "Default")
      (node (ref "UC1") (pin "P$42") (pinfunction "PA9/USART1_TX/TIM1_CH2_P$42") (pintype "bidirectional"))
    )
    (net (code "86") (name "unconnected-(UC1-PA10{slash}USART1_RX{slash}TIM1_CH3-PadP$43)") (class "Default")
      (node (ref "UC1") (pin "P$43") (pinfunction "PA10/USART1_RX/TIM1_CH3_P$43") (pintype "bidirectional"))
    )
    (net (code "87") (name "unconnected-(UC1-PB5{slash}I2C1_SMBA-PadP$57)") (class "Default")
      (node (ref "UC1") (pin "P$57") (pinfunction "PB5/I2C1_SMBA_P$57") (pintype "bidirectional"))
    )
    (net (code "88") (name "unconnected-(UC1-PB6{slash}I2C1_SCL{slash}TIM4_CH1-PadP$58)") (class "Default")
      (node (ref "UC1") (pin "P$58") (pinfunction "PB6/I2C1_SCL/TIM4_CH1_P$58") (pintype "bidirectional"))
    )
    (net (code "89") (name "unconnected-(UC1-PB7{slash}I2C1_SDA{slash}TIM4_CH2-PadP$59)") (class "Default")
      (node (ref "UC1") (pin "P$59") (pinfunction "PB7/I2C1_SDA/TIM4_CH2_P$59") (pintype "bidirectional"))
    )
    (net (code "90") (name "unconnected-(UC1-PB8{slash}TIM4_CH3-PadP$61)") (class "Default")
      (node (ref "UC1") (pin "P$61") (pinfunction "PB8/TIM4_CH3_P$61") (pintype "bidirectional"))
    )
    (net (code "91") (name "unconnected-(UC1-PB9{slash}TIM4_CH4-PadP$62)") (class "Default")
      (node (ref "UC1") (pin "P$62") (pinfunction "PB9/TIM4_CH4_P$62") (pintype "bidirectional"))
    )
    (net (code "92") (name "unconnected-(UC1-PB12{slash}SPI2_NSS{slash}I2C2_SMBAL{slash}USART3_CK{slash}TIM1_BKIN-PadP$33)") (class "Default")
      (node (ref "UC1") (pin "P$33") (pinfunction "PB12/SPI2_NSS/I2C2_SMBAL/USART3_CK/TIM1_BKIN_P$33") (pintype "bidirectional"))
    )
    (net (code "93") (name "unconnected-(UC1-PB13{slash}SPI2_SCK{slash}USART3_CTS{slash}TIM1_CH1N-PadP$34)") (class "Default")
      (node (ref "UC1") (pin "P$34") (pinfunction "PB13/SPI2_SCK/USART3_CTS/TIM1_CH1N_P$34") (pintype "bidirectional"))
    )
    (net (code "94") (name "unconnected-(UC1-PC0{slash}ADC10-PadP$8)") (class "Default")
      (node (ref "UC1") (pin "P$8") (pinfunction "PC0/ADC10_P$8") (pintype "bidirectional"))
    )
    (net (code "95") (name "unconnected-(UC1-PC1{slash}ADC11-PadP$9)") (class "Default")
      (node (ref "UC1") (pin "P$9") (pinfunction "PC1/ADC11_P$9") (pintype "bidirectional"))
    )
    (net (code "96") (name "unconnected-(UC1-PC2{slash}ADC12-PadP$10)") (class "Default")
      (node (ref "UC1") (pin "P$10") (pinfunction "PC2/ADC12_P$10") (pintype "bidirectional"))
    )
    (net (code "97") (name "unconnected-(UC1-PC4{slash}ADC14-PadP$24)") (class "Default")
      (node (ref "UC1") (pin "P$24") (pinfunction "PC4/ADC14_P$24") (pintype "bidirectional"))
    )
    (net (code "98") (name "unconnected-(UC1-PC10-PadP$51)") (class "Default")
      (node (ref "UC1") (pin "P$51") (pinfunction "PC10_P$51") (pintype "bidirectional"))
    )
    (net (code "99") (name "unconnected-(UC1-PC11-PadP$52)") (class "Default")
      (node (ref "UC1") (pin "P$52") (pinfunction "PC11_P$52") (pintype "bidirectional"))
    )
    (net (code "100") (name "unconnected-(UC1-PC12-PadP$53)") (class "Default")
      (node (ref "UC1") (pin "P$53") (pinfunction "PC12_P$53") (pintype "bidirectional"))
    )
    (net (code "101") (name "unconnected-(UC1-PC13-TAMPER-RTC-PadP$2)") (class "Default")
      (node (ref "UC1") (pin "P$2") (pinfunction "PC13-TAMPER-RTC_P$2") (pintype "bidirectional"))
    )
    (net (code "102") (name "unconnected-(UC1-PC14{slash}OSC32_IN-PadP$3)") (class "Default")
      (node (ref "UC1") (pin "P$3") (pinfunction "PC14/OSC32_IN_P$3") (pintype "bidirectional"))
    )
    (net (code "103") (name "unconnected-(UC1-PC15{slash}OSC_OUT-PadP$4)") (class "Default")
      (node (ref "UC1") (pin "P$4") (pinfunction "PC15/OSC_OUT_P$4") (pintype "bidirectional"))
    )
    (net (code "104") (name "unconnected-(UC1-PD2{slash}TIM3-ETR-PadP$54)") (class "Default")
      (node (ref "UC1") (pin "P$54") (pinfunction "PD2/TIM3-ETR_P$54") (pintype "bidirectional"))
    )
    (net (code "105") (name "unconnected-(USB-PadID)") (class "Default")
      (node (ref "USB") (pin "ID") (pinfunction "ID_ID") (pintype "bidirectional"))
    )
  )
)
